# board.net
KiCad netlist of a schematic drawn in EAGLE
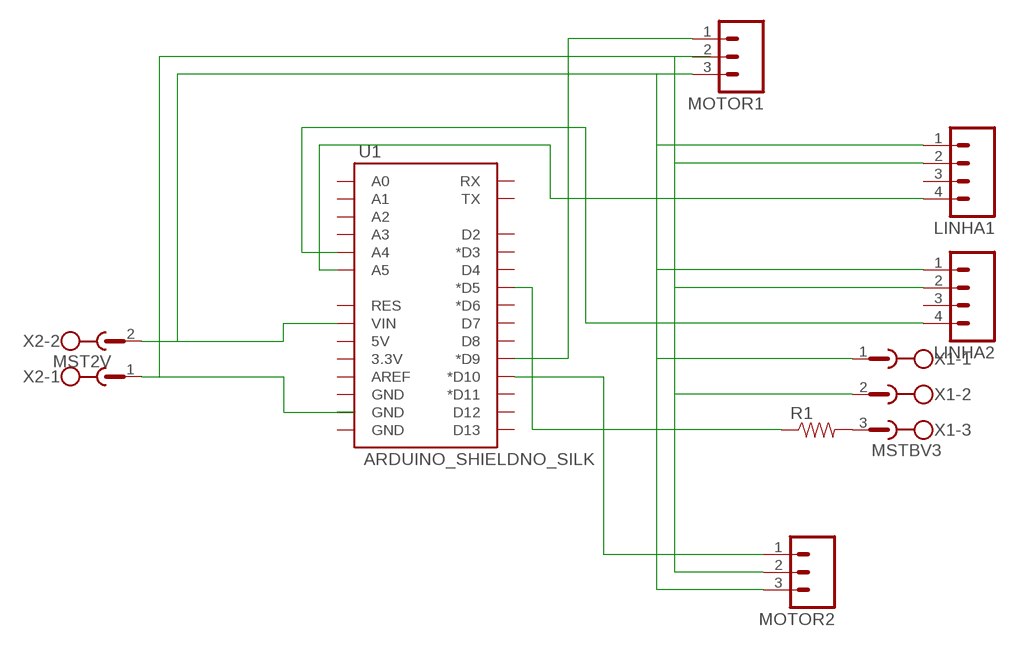
[diagram p0: schematic, sheet 1]

(export (version "E")
  (design (tool "Eeschema 10.0.6"))
  (components
    (comp (ref "LINHA1")
      (value "M04LONGPADS")
      (footprint "eagle-import:1X04_LONGPADS")
      (libsource (lib "eagle-import") (part "M04LONGPADS"))
    )
    (comp (ref "LINHA2")
      (value "M04LONGPADS")
      (footprint "eagle-import:1X04_LONGPADS")
      (libsource (lib "eagle-import") (part "M04LONGPADS"))
    )
    (comp (ref "MOTOR1")
      (value "M03LONGPADS")
      (footprint "eagle-import:1X03_LONGPADS")
      (libsource (lib "eagle-import") (part "M03LONGPADS"))
    )
    (comp (ref "MOTOR2")
      (value "M03LONGPADS")
      (footprint "eagle-import:1X03_LONGPADS")
      (libsource (lib "eagle-import") (part "M03LONGPADS"))
    )
    (comp (ref "R1")
      (value "10KOHM-1/6W-5%(PTH)KIT")
      (footprint "eagle-import:AXIAL-0.3-KIT")
      (libsource (lib "eagle-import") (part "10KOHM-1/6W-5%(PTH)KIT"))
    )
    (comp (ref "U1")
      (value "ARDUINO_SHIELDNO_SILK")
      (footprint "eagle-import:DUEMILANOVE_VIAS")
      (libsource (lib "eagle-import") (part "ARDUINO_SHIELDNO_SILK"))
    )
    (comp (ref "X1")
      (value "MSTBV3")
      (footprint "eagle-import:MSTBV3")
      (fields (field (name "MPN") "MSTBV 2,5/3-GF-5.08"))
      (libsource (lib "eagle-import") (part "MSTBV3"))
    )
    (comp (ref "X2")
      (value "MST2V")
      (footprint "eagle-import:MSTBV2")
      (libsource (lib "eagle-import") (part "MST2V"))
    )
  )
  (nets
    (net (code "1") (name "Net-(LINHA1-Pad4)") (class "Default")
      (node (ref "LINHA1") (pin "4") (pinfunction "4_4") (pintype "passive"))
      (node (ref "U1") (pin "A5") (pinfunction "A5_A5") (pintype "bidirectional"))
    )
    (net (code "2") (name "Net-(LINHA2-Pad4)") (class "Default")
      (node (ref "LINHA2") (pin "4") (pinfunction "4_4") (pintype "passive"))
      (node (ref "U1") (pin "A4") (pinfunction "A4_A4") (pintype "bidirectional"))
    )
    (net (code "3") (name "Net-(R1-1)") (class "Default")
      (node (ref "R1") (pin "P$1") (pinfunction "1_P$1") (pintype "passive"))
      (node (ref "U1") (pin "D5") (pinfunction "*D5_D5") (pintype "bidirectional"))
    )
    (net (code "4") (name "Net-(R1-2)") (class "Default")
      (node (ref "R1") (pin "P$2") (pinfunction "2_P$2") (pintype "passive"))
      (node (ref "X1") (pin "3") (pinfunction "1_3") (pintype "passive"))
    )
    (net (code "5") (name "Net-(U1-*D9)") (class "Default")
      (node (ref "MOTOR1") (pin "1") (pinfunction "1_1") (pintype "passive"))
      (node (ref "U1") (pin "D9") (pinfunction "*D9_D9") (pintype "bidirectional"))
    )
    (net (code "6") (name "Net-(U1-*D10)") (class "Default")
      (node (ref "MOTOR2") (pin "1") (pinfunction "1_1") (pintype "passive"))
      (node (ref "U1") (pin "D10") (pinfunction "*D10_D10") (pintype "bidirectional"))
    )
    (net (code "7") (name "Net-(X1B-1)") (class "Default")
      (node (ref "LINHA1") (pin "2") (pinfunction "2_2") (pintype "passive"))
      (node (ref "LINHA2") (pin "2") (pinfunction "2_2") (pintype "passive"))
      (node (ref "MOTOR2") (pin "2") (pinfunction "2_2") (pintype "passive"))
      (node (ref "U1") (pin "GND@1") (pinfunction "GND_GND@1") (pintype "bidirectional"))
      (node (ref "X1") (pin "2") (pinfunction "1_2") (pintype "passive"))
      (node (ref "X2") (pin "1") (pinfunction "1_1") (pintype "passive"))
    )
    (net (code "8") (name "Net-(X2B-1)") (class "Default")
      (node (ref "LINHA1") (pin "1") (pinfunction "1_1") (pintype "passive"))
      (node (ref "LINHA2") (pin "1") (pinfunction "1_1") (pintype "passive"))
      (node (ref "MOTOR1") (pin "3") (pinfunction "3_3") (pintype "passive"))
      (node (ref "MOTOR2") (pin "3") (pinfunction "3_3") (pintype "passive"))
      (node (ref "U1") (pin "VIN") (pinfunction "VIN_VIN") (pintype "bidirectional"))
      (node (ref "X1") (pin "1") (pinfunction "1_1") (pintype "passive"))
      (node (ref "X2") (pin "2") (pinfunction "1_2") (pintype "passive"))
    )
    (net (code "9") (name "unconnected-(LINHA1-Pad3)") (class "Default")
      (node (ref "LINHA1") (pin "3") (pinfunction "3_3") (pintype "passive"))
    )
    (net (code "10") (name "unconnected-(LINHA2-Pad3)") (class "Default")
      (node (ref "LINHA2") (pin "3") (pinfunction "3_3") (pintype "passive"))
    )
    (net (code "11") (name "unconnected-(MOTOR1-Pad2)") (class "Default")
      (node (ref "MOTOR1") (pin "2") (pinfunction "2_2") (pintype "passive"))
    )
    (net (code "12") (name "unconnected-(U1-*D3-PadD3)") (class "Default")
      (node (ref "U1") (pin "D3") (pinfunction "*D3_D3") (pintype "bidirectional"))
    )
    (net (code "13") (name "unconnected-(U1-*D6-PadD6)") (class "Default")
      (node (ref "U1") (pin "D6") (pinfunction "*D6_D6") (pintype "bidirectional"))
    )
    (net (code "14") (name "unconnected-(U1-*D11-PadD11)") (class "Default")
      (node (ref "U1") (pin "D11") (pinfunction "*D11_D11") (pintype "bidirectional"))
    )
    (net (code "15") (name "unconnected-(U1-GND-PadGND@0)") (class "Default")
      (node (ref "U1") (pin "GND@0") (pinfunction "GND_GND@0") (pintype "bidirectional"))
    )
    (net (code "16") (name "unconnected-(U1-GND-PadGND@2)") (class "Default")
      (node (ref "U1") (pin "GND@2") (pinfunction "GND_GND@2") (pintype "bidirectional"))
    )
    (net (code "17") (name "unconnected-(U1-Pad3.3V)") (class "Default")
      (node (ref "U1") (pin "3.3V") (pinfunction "3.3V_3.3V") (pintype "bidirectional"))
    )
    (net (code "18") (name "unconnected-(U1-Pad5V)") (class "Default")
      (node (ref "U1") (pin "5V") (pinfunction "5V_5V") (pintype "bidirectional"))
    )
    (net (code "19") (name "unconnected-(U1-PadA0)") (class "Default")
      (node (ref "U1") (pin "A0") (pinfunction "A0_A0") (pintype "bidirectional"))
    )
    (net (code "20") (name "unconnected-(U1-PadA1)") (class "Default")
      (node (ref "U1") (pin "A1") (pinfunction "A1_A1") (pintype "bidirectional"))
    )
    (net (code "21") (name "unconnected-(U1-PadA2)") (class "Default")
      (node (ref "U1") (pin "A2") (pinfunction "A2_A2") (pintype "bidirectional"))
    )
    (net (code "22") (name "unconnected-(U1-PadA3)") (class "Default")
      (node (ref "U1") (pin "A3") (pinfunction "A3_A3") (pintype "bidirectional"))
    )
    (net (code "23") (name "unconnected-(U1-PadAREF)") (class "Default")
      (node (ref "U1") (pin "AREF") (pinfunction "AREF_AREF") (pintype "bidirectional"))
    )
    (net (code "24") (name "unconnected-(U1-PadD2)") (class "Default")
      (node (ref "U1") (pin "D2") (pinfunction "D2_D2") (pintype "bidirectional"))
    )
    (net (code "25") (name "unconnected-(U1-PadD4)") (class "Default")
      (node (ref "U1") (pin "D4") (pinfunction "D4_D4") (pintype "bidirectional"))
    )
    (net (code "26") (name "unconnected-(U1-PadD7)") (class "Default")
      (node (ref "U1") (pin "D7") (pinfunction "D7_D7") (pintype "bidirectional"))
    )
    (net (code "27") (name "unconnected-(U1-PadD8)") (class "Default")
      (node (ref "U1") (pin "D8") (pinfunction "D8_D8") (pintype "bidirectional"))
    )
    (net (code "28") (name "unconnected-(U1-PadD12)") (class "Default")
      (node (ref "U1") (pin "D12") (pinfunction "D12_D12") (pintype "bidirectional"))
    )
    (net (code "29") (name "unconnected-(U1-PadD13)") (class "Default")
      (node (ref "U1") (pin "D13") (pinfunction "D13_D13") (pintype "bidirectional"))
    )
    (net (code "30") (name "unconnected-(U1-PadRES)") (class "Default")
      (node (ref "U1") (pin "RES") (pinfunction "RES_RES") (pintype "bidirectional"))
    )
    (net (code "31") (name "unconnected-(U1-PadRX)") (class "Default")
      (node (ref "U1") (pin "RX") (pinfunction "RX_RX") (pintype "bidirectional"))
    )
    (net (code "32") (name "unconnected-(U1-PadTX)") (class "Default")
      (node (ref "U1") (pin "TX") (pinfunction "TX_TX") (pintype "bidirectional"))
    )
  )
)
